# EMGPreamp.net
KiCad netlist of a schematic drawn in EAGLE
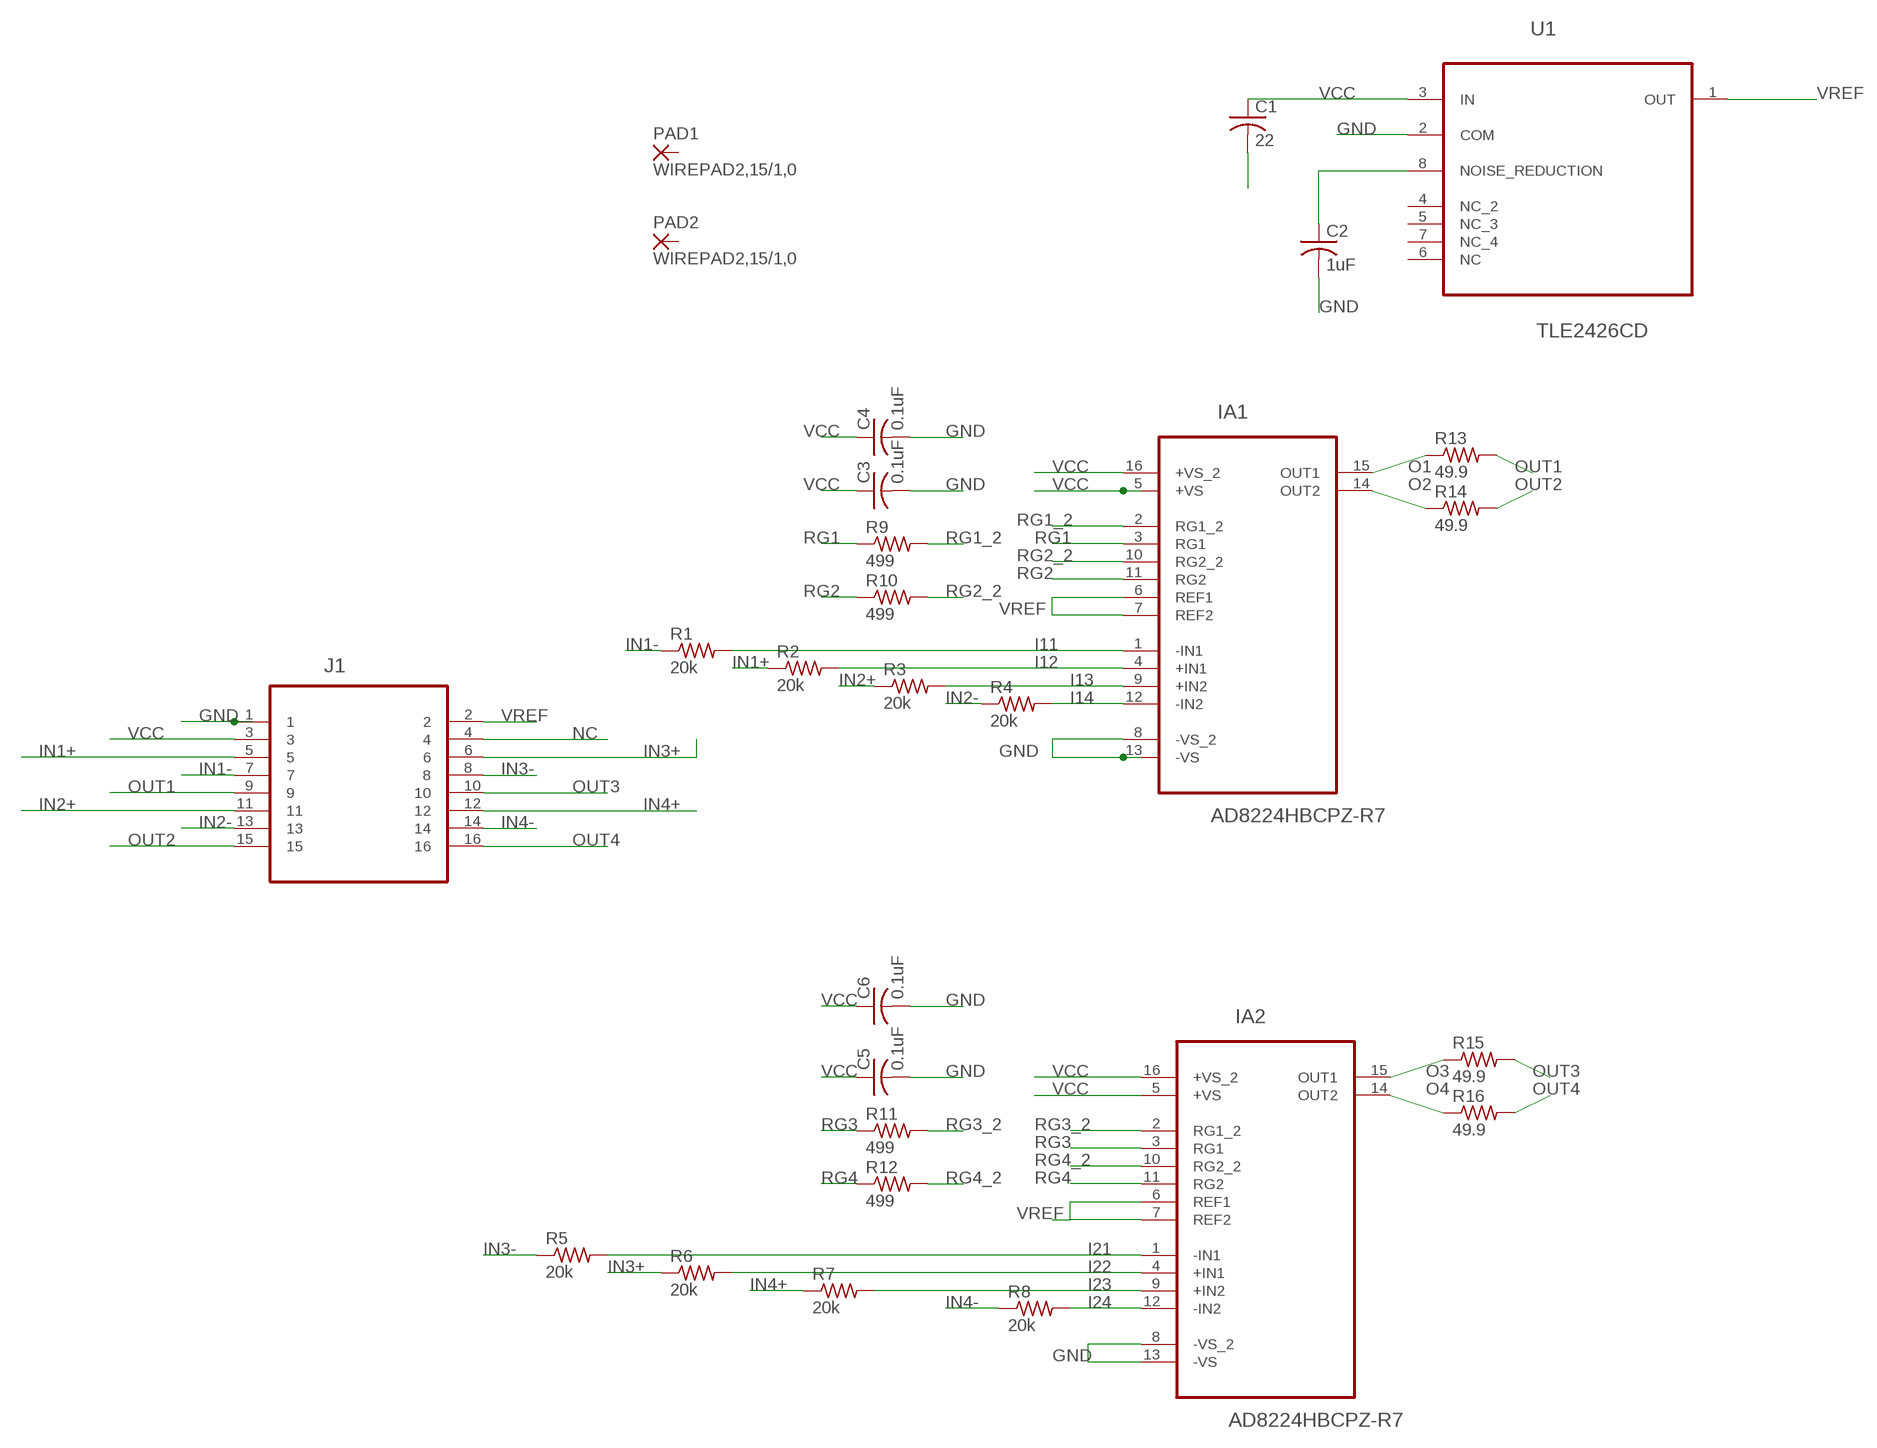
[diagram p0: schematic, sheet 1]

(export (version "E")
  (design (tool "Eeschema 10.0.6"))
  (components
    (comp (ref "C1")
      (value "22")
      (footprint "eagle-import:C0805")
      (libsource (lib "eagle-import") (part "C-USC0805"))
    )
    (comp (ref "C2")
      (value "1uF")
      (footprint "eagle-import:C0805")
      (libsource (lib "eagle-import") (part "C-USC0805"))
    )
    (comp (ref "C3")
      (value "0.1uF")
      (footprint "eagle-import:C0805")
      (libsource (lib "eagle-import") (part "C-USC0805"))
    )
    (comp (ref "C4")
      (value "0.1uF")
      (footprint "eagle-import:C0805")
      (libsource (lib "eagle-import") (part "C-USC0805"))
    )
    (comp (ref "C5")
      (value "0.1uF")
      (footprint "eagle-import:C0805")
      (libsource (lib "eagle-import") (part "C-USC0805"))
    )
    (comp (ref "C6")
      (value "0.1uF")
      (footprint "eagle-import:C0805")
      (libsource (lib "eagle-import") (part "C-USC0805"))
    )
    (comp (ref "IA1")
      (value "AD8224HBCPZ-R7")
      (footprint "eagle-import:QFN65P400X400X100-16N")
      (libsource (lib "eagle-import") (part "AD8224HBCPZ-R7"))
    )
    (comp (ref "IA2")
      (value "AD8224HBCPZ-R7")
      (footprint "eagle-import:QFN65P400X400X100-16N")
      (libsource (lib "eagle-import") (part "AD8224HBCPZ-R7"))
    )
    (comp (ref "J1")
      (value "FTSH-108-01-L-MT")
      (footprint "eagle-import:FTSH-108-1-L-MT")
      (libsource (lib "eagle-import") (part "FTSH-108-01-L-MT"))
    )
    (comp (ref "PAD1")
      (value "WIREPAD2,15/1,0")
      (footprint "eagle-import:2,15_1,0")
      (libsource (lib "eagle-import") (part "WIREPAD2,15/1,0"))
    )
    (comp (ref "PAD2")
      (value "WIREPAD2,15/1,0")
      (footprint "eagle-import:2,15_1,0")
      (libsource (lib "eagle-import") (part "WIREPAD2,15/1,0"))
    )
    (comp (ref "R1")
      (value "20k")
      (footprint "eagle-import:R0805")
      (libsource (lib "eagle-import") (part "R-US_R0805"))
    )
    (comp (ref "R2")
      (value "20k")
      (footprint "eagle-import:R0805")
      (libsource (lib "eagle-import") (part "R-US_R0805"))
    )
    (comp (ref "R3")
      (value "20k")
      (footprint "eagle-import:R0805")
      (libsource (lib "eagle-import") (part "R-US_R0805"))
    )
    (comp (ref "R4")
      (value "20k")
      (footprint "eagle-import:R0805")
      (libsource (lib "eagle-import") (part "R-US_R0805"))
    )
    (comp (ref "R5")
      (value "20k")
      (footprint "eagle-import:R0805")
      (libsource (lib "eagle-import") (part "R-US_R0805"))
    )
    (comp (ref "R6")
      (value "20k")
      (footprint "eagle-import:R0805")
      (libsource (lib "eagle-import") (part "R-US_R0805"))
    )
    (comp (ref "R7")
      (value "20k")
      (footprint "eagle-import:R0805")
      (libsource (lib "eagle-import") (part "R-US_R0805"))
    )
    (comp (ref "R8")
      (value "20k")
      (footprint "eagle-import:R0805")
      (libsource (lib "eagle-import") (part "R-US_R0805"))
    )
    (comp (ref "R9")
      (value "499")
      (footprint "eagle-import:R0805")
      (libsource (lib "eagle-import") (part "R-US_R0805"))
    )
    (comp (ref "R10")
      (value "499")
      (footprint "eagle-import:R0805")
      (libsource (lib "eagle-import") (part "R-US_R0805"))
    )
    (comp (ref "R11")
      (value "499")
      (footprint "eagle-import:R0805")
      (libsource (lib "eagle-import") (part "R-US_R0805"))
    )
    (comp (ref "R12")
      (value "499")
      (footprint "eagle-import:R0805")
      (libsource (lib "eagle-import") (part "R-US_R0805"))
    )
    (comp (ref "R13")
      (value "49.9")
      (footprint "eagle-import:R0805")
      (libsource (lib "eagle-import") (part "R-US_R0805"))
    )
    (comp (ref "R14")
      (value "49.9")
      (footprint "eagle-import:R0805")
      (libsource (lib "eagle-import") (part "R-US_R0805"))
    )
    (comp (ref "R15")
      (value "49.9")
      (footprint "eagle-import:R0805")
      (libsource (lib "eagle-import") (part "R-US_R0805"))
    )
    (comp (ref "R16")
      (value "49.9")
      (footprint "eagle-import:R0805")
      (libsource (lib "eagle-import") (part "R-US_R0805"))
    )
    (comp (ref "U1")
      (value "TLE2426CD")
      (footprint "eagle-import:SOIC127P600X175-8N")
      (libsource (lib "eagle-import") (part "TLE2426CD"))
    )
  )
  (nets
    (net (code "1") (name "/GND") (class "Default")
      (node (ref "C1") (pin "2") (pinfunction "2_2") (pintype "passive"))
      (node (ref "C2") (pin "2") (pinfunction "2_2") (pintype "passive"))
      (node (ref "C3") (pin "2") (pinfunction "2_2") (pintype "passive"))
      (node (ref "C4") (pin "2") (pinfunction "2_2") (pintype "passive"))
      (node (ref "C5") (pin "2") (pinfunction "2_2") (pintype "passive"))
      (node (ref "C6") (pin "2") (pinfunction "2_2") (pintype "passive"))
      (node (ref "IA1") (pin "13") (pinfunction "-VS_13") (pintype "power_in"))
      (node (ref "IA1") (pin "8") (pinfunction "-VS_2_8") (pintype "power_in"))
      (node (ref "IA2") (pin "13") (pinfunction "-VS_13") (pintype "power_in"))
      (node (ref "IA2") (pin "8") (pinfunction "-VS_2_8") (pintype "power_in"))
      (node (ref "J1") (pin "1") (pinfunction "1_1") (pintype "passive"))
      (node (ref "U1") (pin "2") (pinfunction "COM_2") (pintype "passive"))
    )
    (net (code "2") (name "/I11") (class "Default")
      (node (ref "IA1") (pin "1") (pinfunction "-IN1_1") (pintype "input"))
      (node (ref "R1") (pin "2") (pinfunction "2_2") (pintype "passive"))
    )
    (net (code "3") (name "/I12") (class "Default")
      (node (ref "IA1") (pin "4") (pinfunction "+IN1_4") (pintype "input"))
      (node (ref "R2") (pin "2") (pinfunction "2_2") (pintype "passive"))
    )
    (net (code "4") (name "/I13") (class "Default")
      (node (ref "IA1") (pin "9") (pinfunction "+IN2_9") (pintype "input"))
      (node (ref "R3") (pin "2") (pinfunction "2_2") (pintype "passive"))
    )
    (net (code "5") (name "/I14") (class "Default")
      (node (ref "IA1") (pin "12") (pinfunction "-IN2_12") (pintype "input"))
      (node (ref "R4") (pin "2") (pinfunction "2_2") (pintype "passive"))
    )
    (net (code "6") (name "/I21") (class "Default")
      (node (ref "IA2") (pin "1") (pinfunction "-IN1_1") (pintype "input"))
      (node (ref "R5") (pin "2") (pinfunction "2_2") (pintype "passive"))
    )
    (net (code "7") (name "/I22") (class "Default")
      (node (ref "IA2") (pin "4") (pinfunction "+IN1_4") (pintype "input"))
      (node (ref "R6") (pin "2") (pinfunction "2_2") (pintype "passive"))
    )
    (net (code "8") (name "/I23") (class "Default")
      (node (ref "IA2") (pin "9") (pinfunction "+IN2_9") (pintype "input"))
      (node (ref "R7") (pin "2") (pinfunction "2_2") (pintype "passive"))
    )
    (net (code "9") (name "/I24") (class "Default")
      (node (ref "IA2") (pin "12") (pinfunction "-IN2_12") (pintype "input"))
      (node (ref "R8") (pin "2") (pinfunction "2_2") (pintype "passive"))
    )
    (net (code "10") (name "/IN1+") (class "Default")
      (node (ref "J1") (pin "5") (pinfunction "5_5") (pintype "passive"))
      (node (ref "R2") (pin "1") (pinfunction "1_1") (pintype "passive"))
    )
    (net (code "11") (name "/IN1-") (class "Default")
      (node (ref "J1") (pin "7") (pinfunction "7_7") (pintype "passive"))
      (node (ref "R1") (pin "1") (pinfunction "1_1") (pintype "passive"))
    )
    (net (code "12") (name "/IN2+") (class "Default")
      (node (ref "J1") (pin "11") (pinfunction "11_11") (pintype "passive"))
      (node (ref "R3") (pin "1") (pinfunction "1_1") (pintype "passive"))
    )
    (net (code "13") (name "/IN2-") (class "Default")
      (node (ref "J1") (pin "13") (pinfunction "13_13") (pintype "passive"))
      (node (ref "R4") (pin "1") (pinfunction "1_1") (pintype "passive"))
    )
    (net (code "14") (name "/IN3+") (class "Default")
      (node (ref "J1") (pin "6") (pinfunction "6_6") (pintype "passive"))
      (node (ref "R6") (pin "1") (pinfunction "1_1") (pintype "passive"))
    )
    (net (code "15") (name "/IN3-") (class "Default")
      (node (ref "J1") (pin "8") (pinfunction "8_8") (pintype "passive"))
      (node (ref "R5") (pin "1") (pinfunction "1_1") (pintype "passive"))
    )
    (net (code "16") (name "/IN4+") (class "Default")
      (node (ref "J1") (pin "12") (pinfunction "12_12") (pintype "passive"))
      (node (ref "R7") (pin "1") (pinfunction "1_1") (pintype "passive"))
    )
    (net (code "17") (name "/IN4-") (class "Default")
      (node (ref "J1") (pin "14") (pinfunction "14_14") (pintype "passive"))
      (node (ref "R8") (pin "1") (pinfunction "1_1") (pintype "passive"))
    )
    (net (code "18") (name "/NC") (class "Default")
      (node (ref "J1") (pin "4") (pinfunction "4_4") (pintype "passive"))
    )
    (net (code "19") (name "/O1") (class "Default")
      (node (ref "IA1") (pin "15") (pinfunction "OUT1_15") (pintype "output"))
      (node (ref "R13") (pin "1") (pinfunction "1_1") (pintype "passive"))
    )
    (net (code "20") (name "/O2") (class "Default")
      (node (ref "IA1") (pin "14") (pinfunction "OUT2_14") (pintype "output"))
      (node (ref "R14") (pin "1") (pinfunction "1_1") (pintype "passive"))
    )
    (net (code "21") (name "/O3") (class "Default")
      (node (ref "IA2") (pin "15") (pinfunction "OUT1_15") (pintype "output"))
      (node (ref "R15") (pin "1") (pinfunction "1_1") (pintype "passive"))
    )
    (net (code "22") (name "/O4") (class "Default")
      (node (ref "IA2") (pin "14") (pinfunction "OUT2_14") (pintype "output"))
      (node (ref "R16") (pin "1") (pinfunction "1_1") (pintype "passive"))
    )
    (net (code "23") (name "/OUT1") (class "Default")
      (node (ref "J1") (pin "9") (pinfunction "9_9") (pintype "passive"))
      (node (ref "R13") (pin "2") (pinfunction "2_2") (pintype "passive"))
    )
    (net (code "24") (name "/OUT2") (class "Default")
      (node (ref "J1") (pin "15") (pinfunction "15_15") (pintype "passive"))
      (node (ref "R14") (pin "2") (pinfunction "2_2") (pintype "passive"))
    )
    (net (code "25") (name "/OUT3") (class "Default")
      (node (ref "J1") (pin "10") (pinfunction "10_10") (pintype "passive"))
      (node (ref "R15") (pin "2") (pinfunction "2_2") (pintype "passive"))
    )
    (net (code "26") (name "/OUT4") (class "Default")
      (node (ref "J1") (pin "16") (pinfunction "16_16") (pintype "passive"))
      (node (ref "R16") (pin "2") (pinfunction "2_2") (pintype "passive"))
    )
    (net (code "27") (name "/RG1") (class "Default")
      (node (ref "IA1") (pin "3") (pinfunction "RG1_3") (pintype "passive"))
      (node (ref "R9") (pin "1") (pinfunction "1_1") (pintype "passive"))
    )
    (net (code "28") (name "/RG1_2") (class "Default")
      (node (ref "IA1") (pin "2") (pinfunction "RG1_2_2") (pintype "passive"))
      (node (ref "R9") (pin "2") (pinfunction "2_2") (pintype "passive"))
    )
    (net (code "29") (name "/RG2") (class "Default")
      (node (ref "IA1") (pin "11") (pinfunction "RG2_11") (pintype "passive"))
      (node (ref "R10") (pin "1") (pinfunction "1_1") (pintype "passive"))
    )
    (net (code "30") (name "/RG2_2") (class "Default")
      (node (ref "IA1") (pin "10") (pinfunction "RG2_2_10") (pintype "passive"))
      (node (ref "R10") (pin "2") (pinfunction "2_2") (pintype "passive"))
    )
    (net (code "31") (name "/RG3") (class "Default")
      (node (ref "IA2") (pin "3") (pinfunction "RG1_3") (pintype "passive"))
      (node (ref "R11") (pin "1") (pinfunction "1_1") (pintype "passive"))
    )
    (net (code "32") (name "/RG3_2") (class "Default")
      (node (ref "IA2") (pin "2") (pinfunction "RG1_2_2") (pintype "passive"))
      (node (ref "R11") (pin "2") (pinfunction "2_2") (pintype "passive"))
    )
    (net (code "33") (name "/RG4") (class "Default")
      (node (ref "IA2") (pin "11") (pinfunction "RG2_11") (pintype "passive"))
      (node (ref "R12") (pin "1") (pinfunction "1_1") (pintype "passive"))
    )
    (net (code "34") (name "/RG4_2") (class "Default")
      (node (ref "IA2") (pin "10") (pinfunction "RG2_2_10") (pintype "passive"))
      (node (ref "R12") (pin "2") (pinfunction "2_2") (pintype "passive"))
    )
    (net (code "35") (name "/VCC") (class "Default")
      (node (ref "C1") (pin "1") (pinfunction "1_1") (pintype "passive"))
      (node (ref "C3") (pin "1") (pinfunction "1_1") (pintype "passive"))
      (node (ref "C4") (pin "1") (pinfunction "1_1") (pintype "passive"))
      (node (ref "C5") (pin "1") (pinfunction "1_1") (pintype "passive"))
      (node (ref "C6") (pin "1") (pinfunction "1_1") (pintype "passive"))
      (node (ref "IA1") (pin "16") (pinfunction "+VS_2_16") (pintype "power_in"))
      (node (ref "IA1") (pin "5") (pinfunction "+VS_5") (pintype "power_in"))
      (node (ref "IA2") (pin "16") (pinfunction "+VS_2_16") (pintype "power_in"))
      (node (ref "IA2") (pin "5") (pinfunction "+VS_5") (pintype "power_in"))
      (node (ref "J1") (pin "3") (pinfunction "3_3") (pintype "passive"))
      (node (ref "U1") (pin "3") (pinfunction "IN_3") (pintype "input"))
    )
    (net (code "36") (name "/VREF") (class "Default")
      (node (ref "IA1") (pin "6") (pinfunction "REF1_6") (pintype "input"))
      (node (ref "IA1") (pin "7") (pinfunction "REF2_7") (pintype "input"))
      (node (ref "IA2") (pin "6") (pinfunction "REF1_6") (pintype "input"))
      (node (ref "IA2") (pin "7") (pinfunction "REF2_7") (pintype "input"))
      (node (ref "J1") (pin "2") (pinfunction "2_2") (pintype "passive"))
      (node (ref "U1") (pin "1") (pinfunction "OUT_1") (pintype "output"))
    )
    (net (code "37") (name "Net-(U1-NOISE_REDUCTION)") (class "Default")
      (node (ref "C2") (pin "1") (pinfunction "1_1") (pintype "passive"))
      (node (ref "U1") (pin "8") (pinfunction "NOISE_REDUCTION_8") (pintype "passive"))
    )
    (net (code "38") (name "unconnected-(PAD1-P-Pad1)") (class "Default")
      (node (ref "PAD1") (pin "1") (pinfunction "P_1") (pintype "passive"))
    )
    (net (code "39") (name "unconnected-(PAD2-P-Pad1)") (class "Default")
      (node (ref "PAD2") (pin "1") (pinfunction "P_1") (pintype "passive"))
    )
    (net (code "40") (name "unconnected-(U1-NC-Pad6)") (class "Default")
      (node (ref "U1") (pin "6") (pinfunction "NC_6") (pintype "no_connect"))
    )
    (net (code "41") (name "unconnected-(U1-NC_2-Pad4)") (class "Default")
      (node (ref "U1") (pin "4") (pinfunction "NC_2_4") (pintype "no_connect"))
    )
    (net (code "42") (name "unconnected-(U1-NC_3-Pad5)") (class "Default")
      (node (ref "U1") (pin "5") (pinfunction "NC_3_5") (pintype "no_connect"))
    )
    (net (code "43") (name "unconnected-(U1-NC_4-Pad7)") (class "Default")
      (node (ref "U1") (pin "7") (pinfunction "NC_4_7") (pintype "no_connect"))
    )
  )
)
